# treehopper.net
KiCad netlist of a schematic drawn in Altium Designer
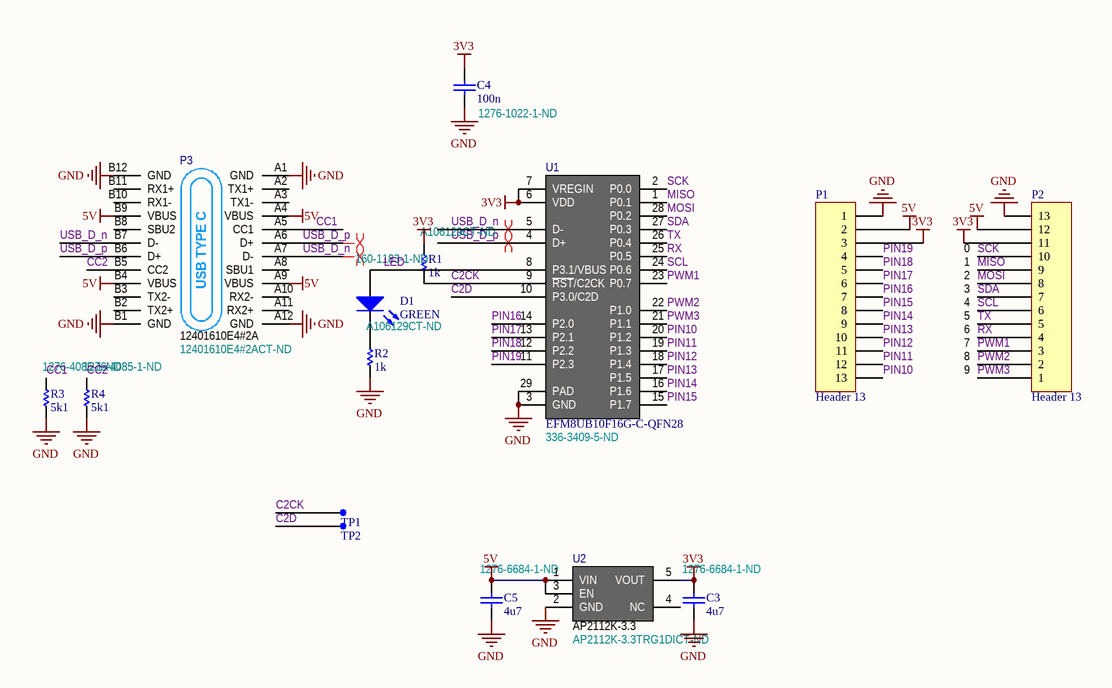
[diagram p0: treehopper.SchDoc]

(export (version "E")
  (design (tool "Eeschema 10.0.6"))
  (components
    (comp (ref "C3")
      (value "4u7")
      (footprint "CAPC1608N")
      (description "CAP SEMI 4U7 10V 0603")
      (fields
        (field (name "SUPPLIER PART NUMBER 1") "1276-6684-1-ND")
        (field (name "PUBLISHER") "Altium Limited")
      )
      (libsource (lib "Miscellaneous Devices") (part "Cap Semi"))
    )
    (comp (ref "C4")
      (value "100n")
      (footprint "CAPC1005N")
      (description "CAP SEMI 0U1 10V 0402")
      (fields
        (field (name "SUPPLIER PART NUMBER 1") "1276-1022-1-ND")
        (field (name "PUBLISHER") "Altium Limited")
      )
      (libsource (lib "Miscellaneous Devices") (part "Cap Semi"))
    )
    (comp (ref "C5")
      (value "4u7")
      (footprint "CAPC1608N")
      (description "CAP SEMI 4U7 10V 0603")
      (fields
        (field (name "SUPPLIER PART NUMBER 1") "1276-6684-1-ND")
        (field (name "PUBLISHER") "Altium Limited")
      )
      (libsource (lib "Miscellaneous Devices") (part "Cap Semi"))
    )
    (comp (ref "D1")
      (value "GREEN")
      (footprint "LTST-C190GKT_NO_SILK")
      (description "LED GREEN 0603")
      (fields
        (field (name "SUPPLIER PART NUMBER 1") "160-1183-1-ND")
        (field (name "PUBLISHER") "Altium Limited")
      )
      (libsource (lib "Miscellaneous Devices") (part "LED_GREEN"))
    )
    (comp (ref "P1")
      (value "Header 13")
      (footprint "HDR1X13CASTELATED")
      (description "DNI")
      (fields (field (name "PUBLISHER") "Altium Limited"))
      (libsource (lib "") (part "Header 13_1"))
    )
    (comp (ref "P2")
      (value "Header 13")
      (footprint "HDR1X13CASTELATED")
      (description "DNI")
      (fields (field (name "PUBLISHER") "Altium Limited"))
      (libsource (lib "Miscellaneous Connectors") (part "Header 13"))
    )
    (comp (ref "P3")
      (value "12401610E4#2A")
      (footprint "12401610E4#2A")
      (description "USB TYPE-C RECEPTACLE")
      (fields
        (field (name "MANUFACTURER") "Amphenol Commercial Products")
        (field (name "SUPPLIER PART NUMBER 1") "12401610E4#2ACT-ND")
      )
      (libsource (lib "Amphenol USB Connector") (part "12401610E4#2A"))
    )
    (comp (ref "R1")
      (value "1k")
      (footprint "RESC1005N")
      (description "RES SEMI 1K 0402")
      (fields
        (field (name "SUPPLIER PART NUMBER 1") "A106129CT-ND")
        (field (name "PUBLISHER") "Altium Limited")
      )
      (libsource (lib "Miscellaneous Devices") (part "Res Semi"))
    )
    (comp (ref "R2")
      (value "1k")
      (footprint "RESC1005N")
      (description "RES SEMI 1K 0402")
      (fields
        (field (name "SUPPLIER PART NUMBER 1") "A106129CT-ND")
        (field (name "PUBLISHER") "Altium Limited")
      )
      (libsource (lib "Miscellaneous Devices") (part "Res Semi"))
    )
    (comp (ref "R3")
      (value "5k1")
      (footprint "RESC1005N")
      (description "RES SEMI 5K1 1% 0402")
      (fields
        (field (name "SUPPLIER PART NUMBER 1") "1276-4085-1-ND")
        (field (name "PUBLISHER") "Altium Limited")
      )
      (libsource (lib "Miscellaneous Devices") (part "Res Semi"))
    )
    (comp (ref "R4")
      (value "5k1")
      (footprint "RESC1005N")
      (description "RES SEMI 5K1 1% 0402")
      (fields
        (field (name "SUPPLIER PART NUMBER 1") "1276-4085-1-ND")
        (field (name "PUBLISHER") "Altium Limited")
      )
      (libsource (lib "Miscellaneous Devices") (part "Res Semi"))
    )
    (comp (ref "TP1")
      (value "TESTPOINT")
      (footprint "TESTPOINT100")
      (description "Testpoint")
      (fields (field (name "PUBLISHER") "Altium Limited"))
      (libsource (lib "Miscellaneous Connectors") (part "TESTPOINT"))
    )
    (comp (ref "TP2")
      (value "TESTPOINT")
      (footprint "TESTPOINT100")
      (description "Testpoint")
      (fields (field (name "PUBLISHER") "Altium Limited"))
      (libsource (lib "Miscellaneous Connectors") (part "TESTPOINT"))
    )
    (comp (ref "U1")
      (value "EFM8UB10F16G-C-QFN28")
      (footprint "QFN50P500X500X80_HS-29N_NO_SILK")
      (description "IC MCU EFM8UB10F16G-C-QFN28 DATE CODE 1601 OR NEWER")
      (fields
        (field (name "MANUFACTURER") "Silicon Labs")
        (field (name "SUPPLIER PART NUMBER 1") "336-3409-5-ND")
      )
      (libsource (lib "SiLabs EFM8 MCU") (part "EFM8UB10F16G-B-QFN28"))
    )
    (comp (ref "U2")
      (value "AP2112K-3.3")
      (footprint "SOT23-5AN-no-silk")
      (description "AP2112 IC REG LDO 3.3V 0.6A SOT25")
      (fields
        (field (name "MANUFACTURER") "Diodes Incorporated")
        (field (name "MANUFACTURER PART NUMBER") "AP2112K-3.3TRG1")
        (field (name "SUPPLIER PART NUMBER 1") "AP2112K-3.3TRG1DICT-ND")
      )
      (libsource (lib "Diodes Inc LDO Regulator") (part "AP2112K-3.3"))
    )
  )
  (nets
    (net (code "1") (name "/C2CK") (class "Default")
      (node (ref "R1") (pin "1") (pinfunction "1_1") (pintype "passive"))
      (node (ref "TP1") (pin "1") (pinfunction "TP_1") (pintype "passive"))
      (node (ref "U1") (pin "9") (pinfunction "~{RST}/C2CK_9") (pintype "passive"))
    )
    (net (code "2") (name "/C2D") (class "Default")
      (node (ref "TP2") (pin "1") (pinfunction "TP_1") (pintype "passive"))
      (node (ref "U1") (pin "10") (pinfunction "P3.0/C2D_10") (pintype "passive"))
    )
    (net (code "3") (name "/CC1") (class "Default")
      (node (ref "P3") (pin "A5") (pinfunction "CC1_A5") (pintype "power_in"))
      (node (ref "R3") (pin "2") (pinfunction "2_2") (pintype "passive"))
    )
    (net (code "4") (name "/CC2") (class "Default")
      (node (ref "P3") (pin "B5") (pinfunction "CC2_B5") (pintype "power_in"))
      (node (ref "R4") (pin "2") (pinfunction "2_2") (pintype "passive"))
    )
    (net (code "5") (name "/LED") (class "Default")
      (node (ref "D1") (pin "1") (pinfunction "A_1") (pintype "passive"))
      (node (ref "U1") (pin "8") (pinfunction "P3.1/VBUS_8") (pintype "passive"))
    )
    (net (code "6") (name "/MISO") (class "Default")
      (node (ref "P2") (pin "9") (pinfunction "9_9") (pintype "passive"))
      (node (ref "U1") (pin "1") (pinfunction "P0.1_1") (pintype "passive"))
    )
    (net (code "7") (name "/MOSI") (class "Default")
      (node (ref "P2") (pin "8") (pinfunction "8_8") (pintype "passive"))
      (node (ref "U1") (pin "28") (pinfunction "P0.2_28") (pintype "passive"))
    )
    (net (code "8") (name "/PIN10") (class "Default")
      (node (ref "P1") (pin "13") (pinfunction "13_13") (pintype "passive"))
      (node (ref "U1") (pin "20") (pinfunction "P1.2_20") (pintype "passive"))
    )
    (net (code "9") (name "/PIN11") (class "Default")
      (node (ref "P1") (pin "12") (pinfunction "12_12") (pintype "passive"))
      (node (ref "U1") (pin "19") (pinfunction "P1.3_19") (pintype "passive"))
    )
    (net (code "10") (name "/PIN12") (class "Default")
      (node (ref "P1") (pin "11") (pinfunction "11_11") (pintype "passive"))
      (node (ref "U1") (pin "18") (pinfunction "P1.4_18") (pintype "passive"))
    )
    (net (code "11") (name "/PIN13") (class "Default")
      (node (ref "P1") (pin "10") (pinfunction "10_10") (pintype "passive"))
      (node (ref "U1") (pin "17") (pinfunction "P1.5_17") (pintype "passive"))
    )
    (net (code "12") (name "/PIN14") (class "Default")
      (node (ref "P1") (pin "9") (pinfunction "9_9") (pintype "passive"))
      (node (ref "U1") (pin "16") (pinfunction "P1.6_16") (pintype "passive"))
    )
    (net (code "13") (name "/PIN15") (class "Default")
      (node (ref "P1") (pin "8") (pinfunction "8_8") (pintype "passive"))
      (node (ref "U1") (pin "15") (pinfunction "P1.7_15") (pintype "passive"))
    )
    (net (code "14") (name "/PIN16") (class "Default")
      (node (ref "P1") (pin "7") (pinfunction "7_7") (pintype "passive"))
      (node (ref "U1") (pin "14") (pinfunction "P2.0_14") (pintype "passive"))
    )
    (net (code "15") (name "/PIN17") (class "Default")
      (node (ref "P1") (pin "6") (pinfunction "6_6") (pintype "passive"))
      (node (ref "U1") (pin "13") (pinfunction "P2.1_13") (pintype "passive"))
    )
    (net (code "16") (name "/PIN18") (class "Default")
      (node (ref "P1") (pin "5") (pinfunction "5_5") (pintype "passive"))
      (node (ref "U1") (pin "12") (pinfunction "P2.2_12") (pintype "passive"))
    )
    (net (code "17") (name "/PIN19") (class "Default")
      (node (ref "P1") (pin "4") (pinfunction "4_4") (pintype "passive"))
      (node (ref "U1") (pin "11") (pinfunction "P2.3_11") (pintype "passive"))
    )
    (net (code "18") (name "/PWM1") (class "Default")
      (node (ref "P2") (pin "3") (pinfunction "3_3") (pintype "passive"))
      (node (ref "U1") (pin "23") (pinfunction "P0.7_23") (pintype "passive"))
    )
    (net (code "19") (name "/PWM2") (class "Default")
      (node (ref "P2") (pin "2") (pinfunction "2_2") (pintype "passive"))
      (node (ref "U1") (pin "22") (pinfunction "P1.0_22") (pintype "passive"))
    )
    (net (code "20") (name "/PWM3") (class "Default")
      (node (ref "P2") (pin "1") (pinfunction "1_1") (pintype "passive"))
      (node (ref "U1") (pin "21") (pinfunction "P1.1_21") (pintype "passive"))
    )
    (net (code "21") (name "/RX") (class "Default")
      (node (ref "P2") (pin "4") (pinfunction "4_4") (pintype "passive"))
      (node (ref "U1") (pin "25") (pinfunction "P0.5_25") (pintype "passive"))
    )
    (net (code "22") (name "/SCK") (class "Default")
      (node (ref "P2") (pin "10") (pinfunction "10_10") (pintype "passive"))
      (node (ref "U1") (pin "2") (pinfunction "P0.0_2") (pintype "passive"))
    )
    (net (code "23") (name "/SCL") (class "Default")
      (node (ref "P2") (pin "6") (pinfunction "6_6") (pintype "passive"))
      (node (ref "U1") (pin "24") (pinfunction "P0.6_24") (pintype "passive"))
    )
    (net (code "24") (name "/SDA") (class "Default")
      (node (ref "P2") (pin "7") (pinfunction "7_7") (pintype "passive"))
      (node (ref "U1") (pin "27") (pinfunction "P0.3_27") (pintype "passive"))
    )
    (net (code "25") (name "/TX") (class "Default")
      (node (ref "P2") (pin "5") (pinfunction "5_5") (pintype "passive"))
      (node (ref "U1") (pin "26") (pinfunction "P0.4_26") (pintype "passive"))
    )
    (net (code "26") (name "/USB_D_n") (class "Default")
      (node (ref "P3") (pin "A7") (pinfunction "D-_A7") (pintype "power_in"))
      (node (ref "P3") (pin "B7") (pinfunction "D-_B7") (pintype "power_in"))
      (node (ref "U1") (pin "5") (pinfunction "D-_5") (pintype "passive"))
    )
    (net (code "27") (name "/USB_D_p") (class "Default")
      (node (ref "P3") (pin "A6") (pinfunction "D+_A6") (pintype "power_in"))
      (node (ref "P3") (pin "B6") (pinfunction "D+_B6") (pintype "power_in"))
      (node (ref "U1") (pin "4") (pinfunction "D+_4") (pintype "passive"))
    )
    (net (code "28") (name "3V3") (class "Default")
      (node (ref "C3") (pin "2") (pinfunction "2_2") (pintype "passive"))
      (node (ref "C4") (pin "2") (pinfunction "2_2") (pintype "passive"))
      (node (ref "P1") (pin "3") (pinfunction "3_3") (pintype "passive"))
      (node (ref "P2") (pin "11") (pinfunction "11_11") (pintype "passive"))
      (node (ref "R1") (pin "2") (pinfunction "2_2") (pintype "passive"))
      (node (ref "U1") (pin "6") (pinfunction "VDD_6") (pintype "passive"))
      (node (ref "U1") (pin "7") (pinfunction "VREGIN_7") (pintype "passive"))
      (node (ref "U2") (pin "5") (pinfunction "VOUT_5") (pintype "passive"))
    )
    (net (code "29") (name "5V") (class "Default")
      (node (ref "C5") (pin "2") (pinfunction "2_2") (pintype "passive"))
      (node (ref "P1") (pin "2") (pinfunction "2_2") (pintype "passive"))
      (node (ref "P2") (pin "12") (pinfunction "12_12") (pintype "passive"))
      (node (ref "P3") (pin "A4") (pinfunction "VBUS_A4") (pintype "power_in"))
      (node (ref "P3") (pin "A9") (pinfunction "VBUS_A9") (pintype "power_in"))
      (node (ref "P3") (pin "B4") (pinfunction "VBUS_B4") (pintype "power_in"))
      (node (ref "P3") (pin "B9") (pinfunction "VBUS_B9") (pintype "power_in"))
      (node (ref "U2") (pin "1") (pinfunction "VIN_1") (pintype "passive"))
      (node (ref "U2") (pin "3") (pinfunction "EN_3") (pintype "passive"))
    )
    (net (code "30") (name "GND") (class "Default")
      (node (ref "C3") (pin "1") (pinfunction "1_1") (pintype "passive"))
      (node (ref "C4") (pin "1") (pinfunction "1_1") (pintype "passive"))
      (node (ref "C5") (pin "1") (pinfunction "1_1") (pintype "passive"))
      (node (ref "P1") (pin "1") (pinfunction "1_1") (pintype "passive"))
      (node (ref "P2") (pin "13") (pinfunction "13_13") (pintype "passive"))
      (node (ref "P3") (pin "A1") (pinfunction "GND_A1") (pintype "power_in"))
      (node (ref "P3") (pin "A12") (pinfunction "GND_A12") (pintype "power_in"))
      (node (ref "P3") (pin "B1") (pinfunction "GND_B1") (pintype "power_in"))
      (node (ref "P3") (pin "B12") (pinfunction "GND_B12") (pintype "power_in"))
      (node (ref "R2") (pin "1") (pinfunction "1_1") (pintype "passive"))
      (node (ref "R3") (pin "1") (pinfunction "1_1") (pintype "passive"))
      (node (ref "R4") (pin "1") (pinfunction "1_1") (pintype "passive"))
      (node (ref "U1") (pin "29") (pinfunction "PAD_29") (pintype "passive"))
      (node (ref "U1") (pin "3") (pinfunction "GND_3") (pintype "passive"))
      (node (ref "U2") (pin "2") (pinfunction "GND_2") (pintype "passive"))
    )
    (net (code "31") (name "Net-(D1-K)") (class "Default")
      (node (ref "D1") (pin "2") (pinfunction "K_2") (pintype "passive"))
      (node (ref "R2") (pin "2") (pinfunction "2_2") (pintype "passive"))
    )
    (net (code "32") (name "unconnected-(P3-RX1+-PadB11)") (class "Default")
      (node (ref "P3") (pin "B11") (pinfunction "RX1+_B11") (pintype "power_in"))
    )
    (net (code "33") (name "unconnected-(P3-RX1--PadB10)") (class "Default")
      (node (ref "P3") (pin "B10") (pinfunction "RX1-_B10") (pintype "power_in"))
    )
    (net (code "34") (name "unconnected-(P3-RX2+-PadA11)") (class "Default")
      (node (ref "P3") (pin "A11") (pinfunction "RX2+_A11") (pintype "power_in"))
    )
    (net (code "35") (name "unconnected-(P3-RX2--PadA10)") (class "Default")
      (node (ref "P3") (pin "A10") (pinfunction "RX2-_A10") (pintype "power_in"))
    )
    (net (code "36") (name "unconnected-(P3-SBU1-PadA8)") (class "Default")
      (node (ref "P3") (pin "A8") (pinfunction "SBU1_A8") (pintype "power_in"))
    )
    (net (code "37") (name "unconnected-(P3-SBU2-PadB8)") (class "Default")
      (node (ref "P3") (pin "B8") (pinfunction "SBU2_B8") (pintype "power_in"))
    )
    (net (code "38") (name "unconnected-(P3-TX1+-PadA2)") (class "Default")
      (node (ref "P3") (pin "A2") (pinfunction "TX1+_A2") (pintype "power_in"))
    )
    (net (code "39") (name "unconnected-(P3-TX1--PadA3)") (class "Default")
      (node (ref "P3") (pin "A3") (pinfunction "TX1-_A3") (pintype "power_in"))
    )
    (net (code "40") (name "unconnected-(P3-TX2+-PadB2)") (class "Default")
      (node (ref "P3") (pin "B2") (pinfunction "TX2+_B2") (pintype "power_in"))
    )
    (net (code "41") (name "unconnected-(P3-TX2--PadB3)") (class "Default")
      (node (ref "P3") (pin "B3") (pinfunction "TX2-_B3") (pintype "power_in"))
    )
    (net (code "42") (name "unconnected-(U2-NC-Pad4)") (class "Default")
      (node (ref "U2") (pin "4") (pinfunction "NC_4") (pintype "passive"))
    )
  )
)
